# keyless_v2_0.net
KiCad netlist of a schematic drawn in EAGLE
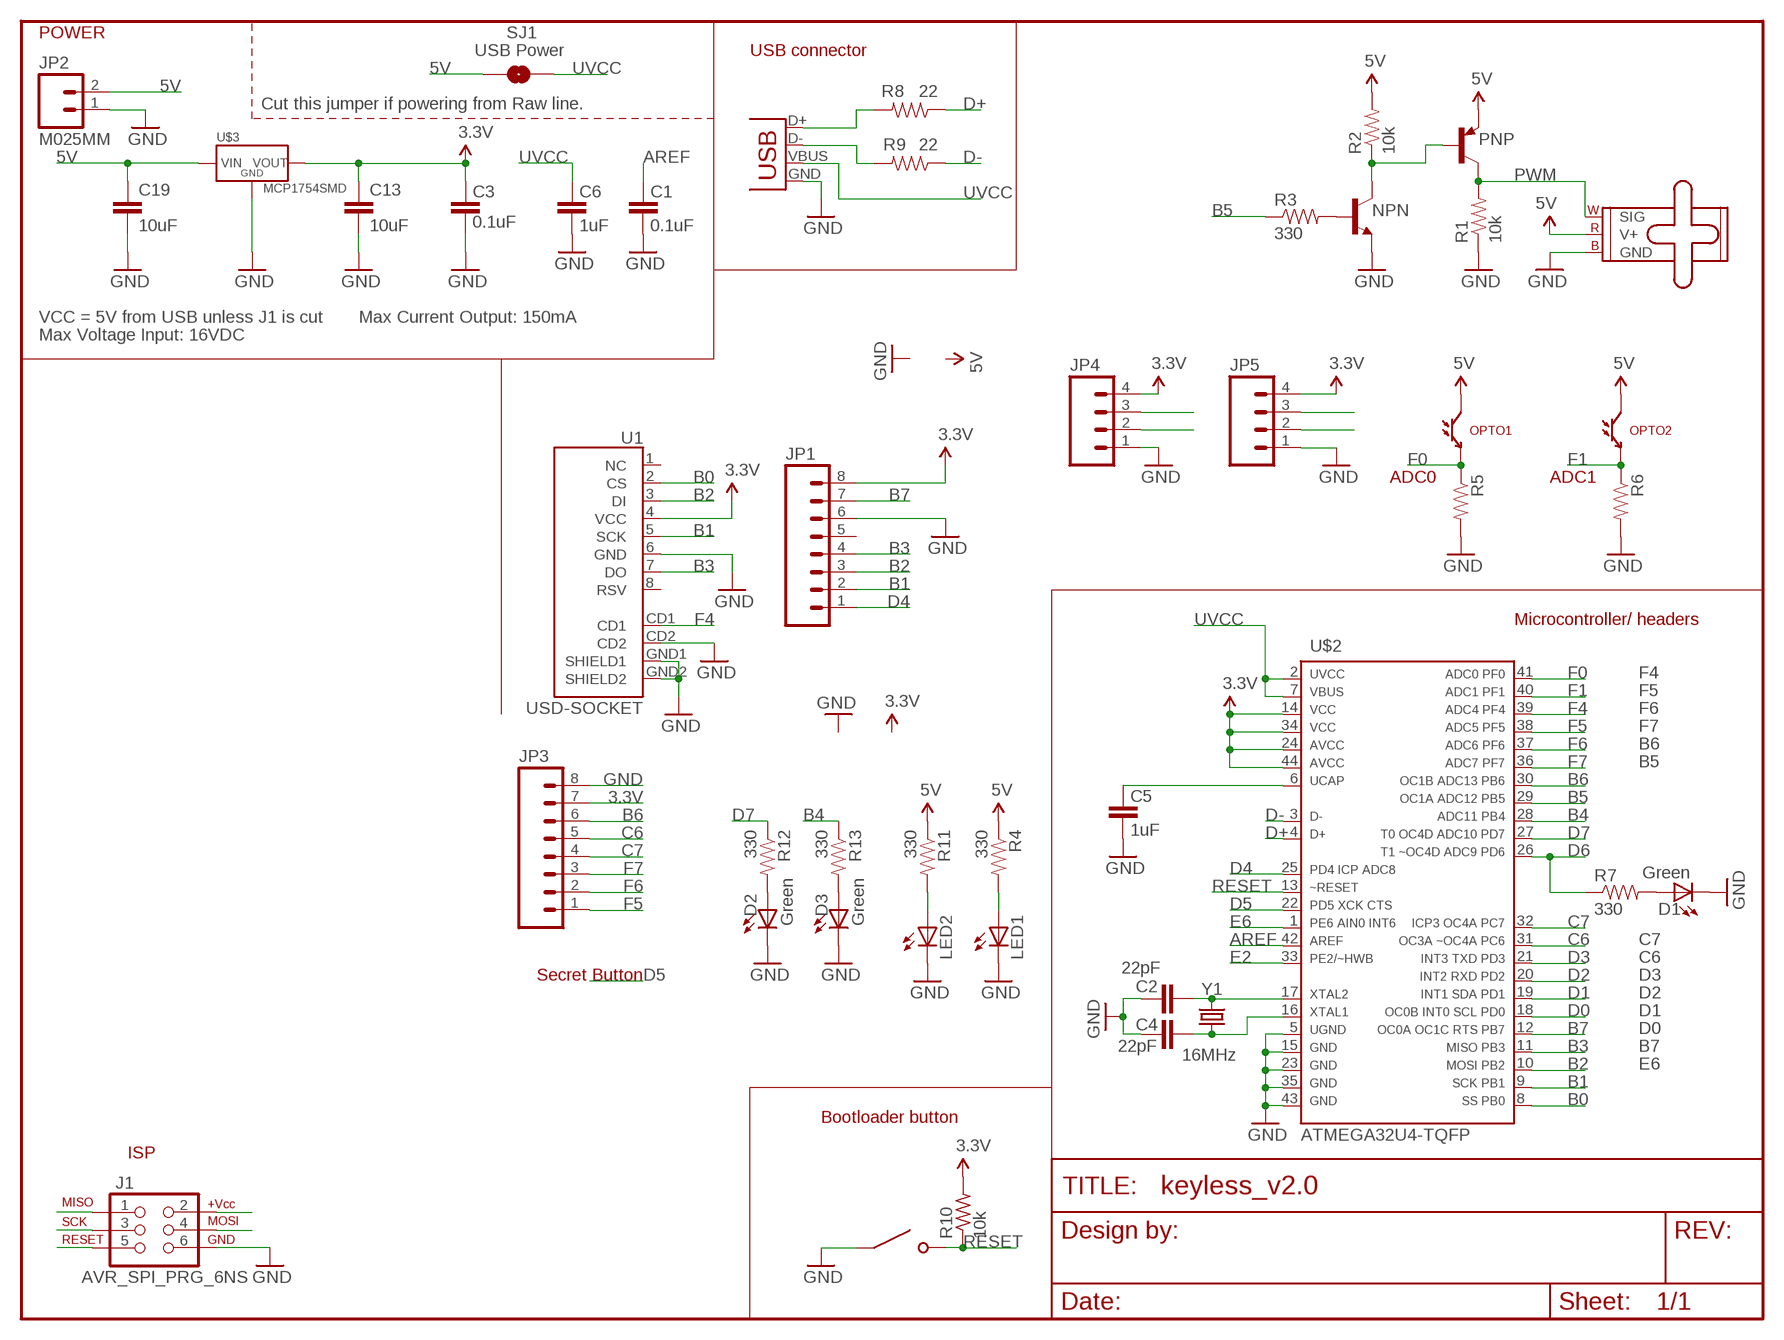
[diagram p0: schematic, sheet 1]

(export (version "E")
  (design (tool "Eeschema 10.0.6"))
  (components
    (comp (ref "C1")
      (value "0.1uF")
      (footprint "eagle-import:0603-CAP")
      (libsource (lib "eagle-import") (part "CAP0603-CAP"))
    )
    (comp (ref "C2")
      (value "22pF")
      (footprint "eagle-import:0805")
      (libsource (lib "eagle-import") (part "CAP0805"))
    )
    (comp (ref "C3")
      (value "0.1uF")
      (footprint "eagle-import:0603-CAP")
      (libsource (lib "eagle-import") (part "CAP0603-CAP"))
    )
    (comp (ref "C4")
      (value "22pF")
      (footprint "eagle-import:0805")
      (libsource (lib "eagle-import") (part "CAP0805"))
    )
    (comp (ref "C5")
      (value "1uF")
      (footprint "eagle-import:0603-CAP")
      (libsource (lib "eagle-import") (part "CAP0603-CAP"))
    )
    (comp (ref "C6")
      (value "1uF")
      (footprint "eagle-import:0603-CAP")
      (libsource (lib "eagle-import") (part "CAP0603-CAP"))
    )
    (comp (ref "C13")
      (value "10uF")
      (footprint "eagle-import:C2012")
      (libsource (lib "eagle-import") (part "C-EUC2012"))
    )
    (comp (ref "C19")
      (value "10uF")
      (footprint "eagle-import:C2012")
      (libsource (lib "eagle-import") (part "C-EUC2012"))
    )
    (comp (ref "D1")
      (value "Green")
      (footprint "eagle-import:CHIP-LED0805")
      (libsource (lib "eagle-import") (part "LEDCHIP-LED0805"))
    )
    (comp (ref "D2")
      (value "Green")
      (footprint "eagle-import:CHIP-LED0805")
      (libsource (lib "eagle-import") (part "LEDCHIP-LED0805"))
    )
    (comp (ref "D3")
      (value "Green")
      (footprint "eagle-import:CHIP-LED0805")
      (libsource (lib "eagle-import") (part "LEDCHIP-LED0805"))
    )
    (comp (ref "FRAME1")
      (value "FRAME-LETTERNONE")
      (footprint "eagle-import:NONE")
      (libsource (lib "eagle-import") (part "FRAME-LETTERNONE"))
    )
    (comp (ref "J1")
      (value "AVR_SPI_PRG_6NS")
      (footprint "eagle-import:2X3-NS")
      (libsource (lib "eagle-import") (part "AVR_SPI_PRG_6NS"))
    )
    (comp (ref "JP1")
      (value "M081X08")
      (footprint "eagle-import:1X08")
      (libsource (lib "eagle-import") (part "M081X08"))
    )
    (comp (ref "JP2")
      (value "M025MM")
      (footprint "eagle-import:SCREWTERMINAL-5MM-2")
      (libsource (lib "eagle-import") (part "M025MM"))
    )
    (comp (ref "JP3")
      (value "M081X08")
      (footprint "eagle-import:1X08")
      (libsource (lib "eagle-import") (part "M081X08"))
    )
    (comp (ref "JP4")
      (value "M04PTH")
      (footprint "eagle-import:1X04")
      (libsource (lib "eagle-import") (part "M04PTH"))
    )
    (comp (ref "JP5")
      (value "M04PTH")
      (footprint "eagle-import:1X04")
      (libsource (lib "eagle-import") (part "M04PTH"))
    )
    (comp (ref "LED1")
      (value "LED5MM")
      (footprint "eagle-import:LED5MM")
      (libsource (lib "eagle-import") (part "LED5MM"))
    )
    (comp (ref "LED2")
      (value "LED5MM")
      (footprint "eagle-import:LED5MM")
      (libsource (lib "eagle-import") (part "LED5MM"))
    )
    (comp (ref "NPN")
      (value "TRANSISTOR_NPNTO-92-AMMO")
      (footprint "eagle-import:TO-92-AMMO")
      (libsource (lib "eagle-import") (part "TRANSISTOR_NPNTO-92-AMMO"))
    )
    (comp (ref "OPTO1")
      (value "LTR-301")
      (footprint "eagle-import:LTR-301")
      (libsource (lib "eagle-import") (part "LTR-301"))
    )
    (comp (ref "OPTO2")
      (value "LTR-301")
      (footprint "eagle-import:LTR-301")
      (libsource (lib "eagle-import") (part "LTR-301"))
    )
    (comp (ref "PNP")
      (value "-PNP-TO92-CEB")
      (footprint "eagle-import:TO92-CEB")
      (libsource (lib "eagle-import") (part "-PNP-TO92-CEB"))
    )
    (comp (ref "R1")
      (value "10k")
      (footprint "eagle-import:AXIAL-0.3")
      (libsource (lib "eagle-import") (part "SparkFun-Passives_RESISTORAXIAL-0.3"))
    )
    (comp (ref "R2")
      (value "10k")
      (footprint "eagle-import:AXIAL-0.3")
      (libsource (lib "eagle-import") (part "SparkFun-Passives_RESISTORAXIAL-0.3"))
    )
    (comp (ref "R3")
      (value "330")
      (footprint "eagle-import:AXIAL-0.3")
      (libsource (lib "eagle-import") (part "SparkFun-Passives_RESISTORAXIAL-0.3"))
    )
    (comp (ref "R4")
      (value "330")
      (footprint "eagle-import:AXIAL-0.3")
      (libsource (lib "eagle-import") (part "SparkFun-Passives_RESISTORAXIAL-0.3"))
    )
    (comp (ref "R5")
      (value "RESISTORAXIAL-0.3")
      (footprint "eagle-import:AXIAL-0.3")
      (libsource (lib "eagle-import") (part "SparkFun-Passives_RESISTORAXIAL-0.3"))
    )
    (comp (ref "R6")
      (value "RESISTORAXIAL-0.3")
      (footprint "eagle-import:AXIAL-0.3")
      (libsource (lib "eagle-import") (part "SparkFun-Passives_RESISTORAXIAL-0.3"))
    )
    (comp (ref "R7")
      (value "330")
      (footprint "eagle-import:0805")
      (libsource (lib "eagle-import") (part "RESISTOR0805-RES"))
    )
    (comp (ref "R8")
      (value "22")
      (footprint "eagle-import:0805")
      (libsource (lib "eagle-import") (part "RESISTOR0805-RES"))
    )
    (comp (ref "R9")
      (value "22")
      (footprint "eagle-import:0805")
      (libsource (lib "eagle-import") (part "RESISTOR0805-RES"))
    )
    (comp (ref "R10")
      (value "10k")
      (footprint "eagle-import:R0603")
      (libsource (lib "eagle-import") (part "R-US_R0603"))
    )
    (comp (ref "R11")
      (value "330")
      (footprint "eagle-import:AXIAL-0.3")
      (libsource (lib "eagle-import") (part "SparkFun-Passives_RESISTORAXIAL-0.3"))
    )
    (comp (ref "R12")
      (value "330")
      (footprint "eagle-import:0805")
      (libsource (lib "eagle-import") (part "RESISTOR0805-RES"))
    )
    (comp (ref "R13")
      (value "330")
      (footprint "eagle-import:0805")
      (libsource (lib "eagle-import") (part "RESISTOR0805-RES"))
    )
    (comp (ref "SERVO")
      (value "SMALL_SERVO")
      (footprint "eagle-import:1X03")
      (libsource (lib "eagle-import") (part "SMALL_SERVO"))
    )
    (comp (ref "SJ1")
      (value "USB Power")
      (footprint "eagle-import:SJ_2S-TRACE")
      (libsource (lib "eagle-import") (part "SOLDERJUMPERTRACE"))
    )
    (comp (ref "U$1")
      (value "MINI-SPDT")
      (footprint "eagle-import:2-PIN-MINI-PUSHBUTTON")
      (libsource (lib "eagle-import") (part "MINI-SPDT"))
    )
    (comp (ref "U$2")
      (value "ATMEGA32U4-TQFP")
      (footprint "eagle-import:TQFP44")
      (libsource (lib "eagle-import") (part "ATMEGA32U4-TQFP"))
    )
    (comp (ref "U$3")
      (value "MCP1754SMD")
      (footprint "eagle-import:SOT23-3")
      (libsource (lib "eagle-import") (part "MCP1754SMD"))
    )
    (comp (ref "U1")
      (value "USD-SOCKET")
      (footprint "eagle-import:USD-SOCKET-DX")
      (libsource (lib "eagle-import") (part "USD-SOCKET"))
    )
    (comp (ref "X1")
      (value "USB-SMD-NS")
      (footprint "eagle-import:USB-MINIB-NOHOLE")
      (libsource (lib "eagle-import") (part "USB-SMD-NS"))
    )
    (comp (ref "Y1")
      (value "16MHz")
      (footprint "eagle-import:ABM2-8X4.5-CRYSTAL")
      (libsource (lib "eagle-import") (part "CRYSTAL"))
    )
  )
  (nets
    (net (code "1") (name "/AREF") (class "Default")
      (node (ref "C1") (pin "2") (pinfunction "2_2") (pintype "passive"))
      (node (ref "U$2") (pin "42") (pinfunction "P$42_42") (pintype "bidirectional"))
    )
    (net (code "2") (name "/B0") (class "Default")
      (node (ref "U$2") (pin "8") (pinfunction "P$8_8") (pintype "bidirectional"))
      (node (ref "U1") (pin "2") (pinfunction "CS_2") (pintype "bidirectional"))
    )
    (net (code "3") (name "/B1") (class "Default")
      (node (ref "J1") (pin "3") (pinfunction "3_3") (pintype "passive"))
      (node (ref "JP1") (pin "2") (pinfunction "2_2") (pintype "passive"))
      (node (ref "U$2") (pin "9") (pinfunction "P$9_9") (pintype "bidirectional"))
      (node (ref "U1") (pin "5") (pinfunction "SCK_5") (pintype "bidirectional"))
    )
    (net (code "4") (name "/B2") (class "Default")
      (node (ref "J1") (pin "4") (pinfunction "4_4") (pintype "passive"))
      (node (ref "JP1") (pin "3") (pinfunction "3_3") (pintype "passive"))
      (node (ref "U$2") (pin "10") (pinfunction "P$10_10") (pintype "bidirectional"))
      (node (ref "U1") (pin "3") (pinfunction "DI_3") (pintype "bidirectional"))
    )
    (net (code "5") (name "/B3") (class "Default")
      (node (ref "J1") (pin "1") (pinfunction "1_1") (pintype "passive"))
      (node (ref "JP1") (pin "4") (pinfunction "4_4") (pintype "passive"))
      (node (ref "U$2") (pin "11") (pinfunction "P$11_11") (pintype "bidirectional"))
      (node (ref "U1") (pin "7") (pinfunction "DO_7") (pintype "bidirectional"))
    )
    (net (code "6") (name "/B4") (class "Default")
      (node (ref "R13") (pin "1") (pinfunction "1_1") (pintype "passive"))
      (node (ref "U$2") (pin "28") (pinfunction "P$28_28") (pintype "bidirectional"))
    )
    (net (code "7") (name "/B5") (class "Default")
      (node (ref "R3") (pin "P$1") (pinfunction "1_P$1") (pintype "passive"))
      (node (ref "U$2") (pin "29") (pinfunction "P$29_29") (pintype "bidirectional"))
    )
    (net (code "8") (name "/B6") (class "Default")
      (node (ref "JP3") (pin "6") (pinfunction "6_6") (pintype "passive"))
      (node (ref "U$2") (pin "30") (pinfunction "P$30_30") (pintype "bidirectional"))
    )
    (net (code "9") (name "/B7") (class "Default")
      (node (ref "JP1") (pin "7") (pinfunction "7_7") (pintype "passive"))
      (node (ref "U$2") (pin "12") (pinfunction "P$12_12") (pintype "bidirectional"))
    )
    (net (code "10") (name "/C6") (class "Default")
      (node (ref "JP3") (pin "5") (pinfunction "5_5") (pintype "passive"))
      (node (ref "U$2") (pin "31") (pinfunction "P$31_31") (pintype "bidirectional"))
    )
    (net (code "11") (name "/C7") (class "Default")
      (node (ref "JP3") (pin "4") (pinfunction "4_4") (pintype "passive"))
      (node (ref "U$2") (pin "32") (pinfunction "P$32_32") (pintype "bidirectional"))
    )
    (net (code "12") (name "/D+") (class "Default")
      (node (ref "R8") (pin "1") (pinfunction "1_1") (pintype "passive"))
      (node (ref "U$2") (pin "4") (pinfunction "P$4_4") (pintype "bidirectional"))
    )
    (net (code "13") (name "/D-") (class "Default")
      (node (ref "R9") (pin "1") (pinfunction "1_1") (pintype "passive"))
      (node (ref "U$2") (pin "3") (pinfunction "P$3_3") (pintype "bidirectional"))
    )
    (net (code "14") (name "/D0") (class "Default")
      (node (ref "JP5") (pin "2") (pinfunction "2_2") (pintype "passive"))
      (node (ref "U$2") (pin "18") (pinfunction "P$18_18") (pintype "bidirectional"))
    )
    (net (code "15") (name "/D1") (class "Default")
      (node (ref "JP5") (pin "3") (pinfunction "3_3") (pintype "passive"))
      (node (ref "U$2") (pin "19") (pinfunction "P$19_19") (pintype "bidirectional"))
    )
    (net (code "16") (name "/D2") (class "Default")
      (node (ref "JP4") (pin "2") (pinfunction "2_2") (pintype "passive"))
      (node (ref "U$2") (pin "20") (pinfunction "P$20_20") (pintype "bidirectional"))
    )
    (net (code "17") (name "/D3") (class "Default")
      (node (ref "JP4") (pin "3") (pinfunction "3_3") (pintype "passive"))
      (node (ref "U$2") (pin "21") (pinfunction "P$21_21") (pintype "bidirectional"))
    )
    (net (code "18") (name "/D4") (class "Default")
      (node (ref "JP1") (pin "1") (pinfunction "1_1") (pintype "passive"))
      (node (ref "U$2") (pin "25") (pinfunction "P$25_25") (pintype "bidirectional"))
    )
    (net (code "19") (name "/D5") (class "Default")
      (node (ref "U$2") (pin "22") (pinfunction "P$22_22") (pintype "bidirectional"))
    )
    (net (code "20") (name "/D6") (class "Default")
      (node (ref "R7") (pin "1") (pinfunction "1_1") (pintype "passive"))
      (node (ref "U$2") (pin "26") (pinfunction "P$26_26") (pintype "bidirectional"))
    )
    (net (code "21") (name "/D7") (class "Default")
      (node (ref "R12") (pin "1") (pinfunction "1_1") (pintype "passive"))
      (node (ref "U$2") (pin "27") (pinfunction "P$27_27") (pintype "bidirectional"))
    )
    (net (code "22") (name "/E2") (class "Default")
      (node (ref "U$2") (pin "33") (pinfunction "P$33_33") (pintype "bidirectional"))
    )
    (net (code "23") (name "/E6") (class "Default")
      (node (ref "U$2") (pin "1") (pinfunction "P$1_1") (pintype "bidirectional"))
    )
    (net (code "24") (name "/F0") (class "Default")
      (node (ref "OPTO1") (pin "E") (pinfunction "E_E") (pintype "bidirectional"))
      (node (ref "R5") (pin "P$1") (pinfunction "1_P$1") (pintype "passive"))
      (node (ref "U$2") (pin "41") (pinfunction "P$41_41") (pintype "bidirectional"))
    )
    (net (code "25") (name "/F1") (class "Default")
      (node (ref "OPTO2") (pin "E") (pinfunction "E_E") (pintype "bidirectional"))
      (node (ref "R6") (pin "P$1") (pinfunction "1_P$1") (pintype "passive"))
      (node (ref "U$2") (pin "40") (pinfunction "P$40_40") (pintype "bidirectional"))
    )
    (net (code "26") (name "/F4") (class "Default")
      (node (ref "U$2") (pin "39") (pinfunction "P$39_39") (pintype "bidirectional"))
      (node (ref "U1") (pin "CD1") (pinfunction "CD1_CD1") (pintype "bidirectional"))
    )
    (net (code "27") (name "/F5") (class "Default")
      (node (ref "JP3") (pin "1") (pinfunction "1_1") (pintype "passive"))
      (node (ref "U$2") (pin "38") (pinfunction "P$38_38") (pintype "bidirectional"))
    )
    (net (code "28") (name "/F6") (class "Default")
      (node (ref "JP3") (pin "2") (pinfunction "2_2") (pintype "passive"))
      (node (ref "U$2") (pin "37") (pinfunction "P$37_37") (pintype "bidirectional"))
    )
    (net (code "29") (name "/F7") (class "Default")
      (node (ref "JP3") (pin "3") (pinfunction "3_3") (pintype "passive"))
      (node (ref "U$2") (pin "36") (pinfunction "P$36_36") (pintype "bidirectional"))
    )
    (net (code "30") (name "/PWM") (class "Default")
      (node (ref "PNP") (pin "C") (pinfunction "C_C") (pintype "passive"))
      (node (ref "R1") (pin "P$2") (pinfunction "2_P$2") (pintype "passive"))
      (node (ref "SERVO") (pin "1") (pinfunction "SIG_1") (pintype "bidirectional"))
    )
    (net (code "31") (name "/RESET") (class "Default")
      (node (ref "J1") (pin "5") (pinfunction "5_5") (pintype "passive"))
      (node (ref "R10") (pin "1") (pinfunction "1_1") (pintype "passive"))
      (node (ref "U$1") (pin "P$2") (pinfunction "P$2_P$2") (pintype "bidirectional"))
      (node (ref "U$2") (pin "13") (pinfunction "P$13_13") (pintype "bidirectional"))
    )
    (net (code "32") (name "/UVCC") (class "Default")
      (node (ref "C6") (pin "2") (pinfunction "2_2") (pintype "passive"))
      (node (ref "SJ1") (pin "2") (pinfunction "2_2") (pintype "passive"))
      (node (ref "U$2") (pin "2") (pinfunction "P$2_2") (pintype "bidirectional"))
      (node (ref "U$2") (pin "7") (pinfunction "P$7_7") (pintype "bidirectional"))
      (node (ref "X1") (pin "VBUS") (pinfunction "VBUS_VBUS") (pintype "bidirectional"))
    )
    (net (code "33") (name "3.3V") (class "Default")
      (node (ref "C13") (pin "1") (pinfunction "1_1") (pintype "passive"))
      (node (ref "C3") (pin "2") (pinfunction "2_2") (pintype "passive"))
      (node (ref "J1") (pin "2") (pinfunction "2_2") (pintype "passive"))
      (node (ref "JP1") (pin "8") (pinfunction "8_8") (pintype "passive"))
      (node (ref "JP3") (pin "7") (pinfunction "7_7") (pintype "passive"))
      (node (ref "JP4") (pin "4") (pinfunction "4_4") (pintype "passive"))
      (node (ref "JP5") (pin "4") (pinfunction "4_4") (pintype "passive"))
      (node (ref "R10") (pin "2") (pinfunction "2_2") (pintype "passive"))
      (node (ref "U$2") (pin "14") (pinfunction "P$14_14") (pintype "bidirectional"))
      (node (ref "U$2") (pin "24") (pinfunction "P$24_24") (pintype "bidirectional"))
      (node (ref "U$2") (pin "34") (pinfunction "P$34_34") (pintype "bidirectional"))
      (node (ref "U$2") (pin "44") (pinfunction "P$44_44") (pintype "bidirectional"))
      (node (ref "U$3") (pin "2") (pinfunction "VO_2") (pintype "bidirectional"))
      (node (ref "U1") (pin "4") (pinfunction "VCC_4") (pintype "bidirectional"))
    )
    (net (code "34") (name "5V") (class "Default")
      (node (ref "C19") (pin "1") (pinfunction "1_1") (pintype "passive"))
      (node (ref "JP2") (pin "2") (pinfunction "2_2") (pintype "passive"))
      (node (ref "OPTO1") (pin "C") (pinfunction "C_C") (pintype "bidirectional"))
      (node (ref "OPTO2") (pin "C") (pinfunction "C_C") (pintype "bidirectional"))
      (node (ref "PNP") (pin "E") (pinfunction "E_E") (pintype "passive"))
      (node (ref "R11") (pin "P$1") (pinfunction "1_P$1") (pintype "passive"))
      (node (ref "R2") (pin "P$2") (pinfunction "2_P$2") (pintype "passive"))
      (node (ref "R4") (pin "P$1") (pinfunction "1_P$1") (pintype "passive"))
      (node (ref "SERVO") (pin "2") (pinfunction "V+_2") (pintype "bidirectional"))
      (node (ref "SJ1") (pin "1") (pinfunction "1_1") (pintype "passive"))
      (node (ref "U$3") (pin "3") (pinfunction "VCC_3") (pintype "bidirectional"))
    )
    (net (code "35") (name "GND") (class "Default")
      (node (ref "C1") (pin "1") (pinfunction "1_1") (pintype "passive"))
      (node (ref "C13") (pin "2") (pinfunction "2_2") (pintype "passive"))
      (node (ref "C19") (pin "2") (pinfunction "2_2") (pintype "passive"))
      (node (ref "C2") (pin "2") (pinfunction "2_2") (pintype "passive"))
      (node (ref "C3") (pin "1") (pinfunction "1_1") (pintype "passive"))
      (node (ref "C4") (pin "2") (pinfunction "2_2") (pintype "passive"))
      (node (ref "C5") (pin "1") (pinfunction "1_1") (pintype "passive"))
      (node (ref "C6") (pin "1") (pinfunction "1_1") (pintype "passive"))
      (node (ref "D1") (pin "C") (pinfunction "C_C") (pintype "passive"))
      (node (ref "D2") (pin "C") (pinfunction "C_C") (pintype "passive"))
      (node (ref "D3") (pin "C") (pinfunction "C_C") (pintype "passive"))
      (node (ref "J1") (pin "6") (pinfunction "6_6") (pintype "passive"))
      (node (ref "JP1") (pin "6") (pinfunction "6_6") (pintype "passive"))
      (node (ref "JP2") (pin "1") (pinfunction "1_1") (pintype "passive"))
      (node (ref "JP3") (pin "8") (pinfunction "8_8") (pintype "passive"))
      (node (ref "JP4") (pin "1") (pinfunction "1_1") (pintype "passive"))
      (node (ref "JP5") (pin "1") (pinfunction "1_1") (pintype "passive"))
      (node (ref "LED1") (pin "K") (pinfunction "C_K") (pintype "passive"))
      (node (ref "LED2") (pin "K") (pinfunction "C_K") (pintype "passive"))
      (node (ref "NPN") (pin "1") (pinfunction "E_1") (pintype "passive"))
      (node (ref "R1") (pin "P$1") (pinfunction "1_P$1") (pintype "passive"))
      (node (ref "R5") (pin "P$2") (pinfunction "2_P$2") (pintype "passive"))
      (node (ref "R6") (pin "P$2") (pinfunction "2_P$2") (pintype "passive"))
      (node (ref "SERVO") (pin "3") (pinfunction "GND_3") (pintype "bidirectional"))
      (node (ref "U$1") (pin "P$1") (pinfunction "P$1_P$1") (pintype "bidirectional"))
      (node (ref "U$2") (pin "15") (pinfunction "P$15_15") (pintype "bidirectional"))
      (node (ref "U$2") (pin "23") (pinfunction "P$23_23") (pintype "bidirectional"))
      (node (ref "U$2") (pin "35") (pinfunction "P$35_35") (pintype "bidirectional"))
      (node (ref "U$2") (pin "43") (pinfunction "P$43_43") (pintype "bidirectional"))
      (node (ref "U$2") (pin "5") (pinfunction "P$5_5") (pintype "bidirectional"))
      (node (ref "U$3") (pin "1") (pinfunction "GND_1") (pintype "bidirectional"))
      (node (ref "U1") (pin "6") (pinfunction "GND_6") (pintype "bidirectional"))
      (node (ref "U1") (pin "CD2") (pinfunction "CD2_CD2") (pintype "bidirectional"))
      (node (ref "U1") (pin "GND1") (pinfunction "SHIELD1_GND1") (pintype "bidirectional"))
      (node (ref "U1") (pin "GND2") (pinfunction "SHIELD2_GND2") (pintype "bidirectional"))
      (node (ref "X1") (pin "GND") (pinfunction "GND_GND") (pintype "bidirectional"))
    )
    (net (code "36") (name "Net-(D1-PadA)") (class "Default")
      (node (ref "D1") (pin "A") (pinfunction "A_A") (pintype "passive"))
      (node (ref "R7") (pin "2") (pinfunction "2_2") (pintype "passive"))
    )
    (net (code "37") (name "Net-(D2-PadA)") (class "Default")
      (node (ref "D2") (pin "A") (pinfunction "A_A") (pintype "passive"))
      (node (ref "R12") (pin "2") (pinfunction "2_2") (pintype "passive"))
    )
    (net (code "38") (name "Net-(D3-PadA)") (class "Default")
      (node (ref "D3") (pin "A") (pinfunction "A_A") (pintype "passive"))
      (node (ref "R13") (pin "2") (pinfunction "2_2") (pintype "passive"))
    )
    (net (code "39") (name "Net-(NPN-B)") (class "Default")
      (node (ref "NPN") (pin "2") (pinfunction "B_2") (pintype "passive"))
      (node (ref "R3") (pin "P$2") (pinfunction "2_P$2") (pintype "passive"))
    )
    (net (code "40") (name "Net-(NPN-C)") (class "Default")
      (node (ref "NPN") (pin "3") (pinfunction "C_3") (pintype "passive"))
      (node (ref "PNP") (pin "B") (pinfunction "B_B") (pintype "passive"))
      (node (ref "R2") (pin "P$1") (pinfunction "1_P$1") (pintype "passive"))
    )
    (net (code "41") (name "Net-(R4-2)") (class "Default")
      (node (ref "LED1") (pin "A") (pinfunction "A_A") (pintype "passive"))
      (node (ref "R4") (pin "P$2") (pinfunction "2_P$2") (pintype "passive"))
    )
    (net (code "42") (name "Net-(R8-Pad2)") (class "Default")
      (node (ref "R8") (pin "2") (pinfunction "2_2") (pintype "passive"))
      (node (ref "X1") (pin "D+") (pinfunction "D+_D+") (pintype "bidirectional"))
    )
    (net (code "43") (name "Net-(R9-Pad2)") (class "Default")
      (node (ref "R9") (pin "2") (pinfunction "2_2") (pintype "passive"))
      (node (ref "X1") (pin "D-") (pinfunction "D-_D-") (pintype "bidirectional"))
    )
    (net (code "44") (name "Net-(R11-2)") (class "Default")
      (node (ref "LED2") (pin "A") (pinfunction "A_A") (pintype "passive"))
      (node (ref "R11") (pin "P$2") (pinfunction "2_P$2") (pintype "passive"))
    )
    (net (code "45") (name "Net-(U$2-P$6)") (class "Default")
      (node (ref "C5") (pin "2") (pinfunction "2_2") (pintype "passive"))
      (node (ref "U$2") (pin "6") (pinfunction "P$6_6") (pintype "bidirectional"))
    )
    (net (code "46") (name "Net-(U$2-P$16)") (class "Default")
      (node (ref "C4") (pin "1") (pinfunction "1_1") (pintype "passive"))
      (node (ref "U$2") (pin "16") (pinfunction "P$16_16") (pintype "bidirectional"))
      (node (ref "Y1") (pin "P$1") (pinfunction "1_P$1") (pintype "passive"))
    )
    (net (code "47") (name "Net-(U$2-P$17)") (class "Default")
      (node (ref "C2") (pin "1") (pinfunction "1_1") (pintype "passive"))
      (node (ref "U$2") (pin "17") (pinfunction "P$17_17") (pintype "bidirectional"))
      (node (ref "Y1") (pin "P$2") (pinfunction "2_P$2") (pintype "passive"))
    )
    (net (code "48") (name "unconnected-(JP1-Pad5)") (class "Default")
      (node (ref "JP1") (pin "5") (pinfunction "5_5") (pintype "passive"))
    )
    (net (code "49") (name "unconnected-(U1-NC-Pad1)") (class "Default")
      (node (ref "U1") (pin "1") (pinfunction "NC_1") (pintype "bidirectional"))
    )
    (net (code "50") (name "unconnected-(U1-RSV-Pad8)") (class "Default")
      (node (ref "U1") (pin "8") (pinfunction "RSV_8") (pintype "bidirectional"))
    )
  )
)
